# button_control_esp32.net
KiCad netlist of a schematic drawn in EAGLE
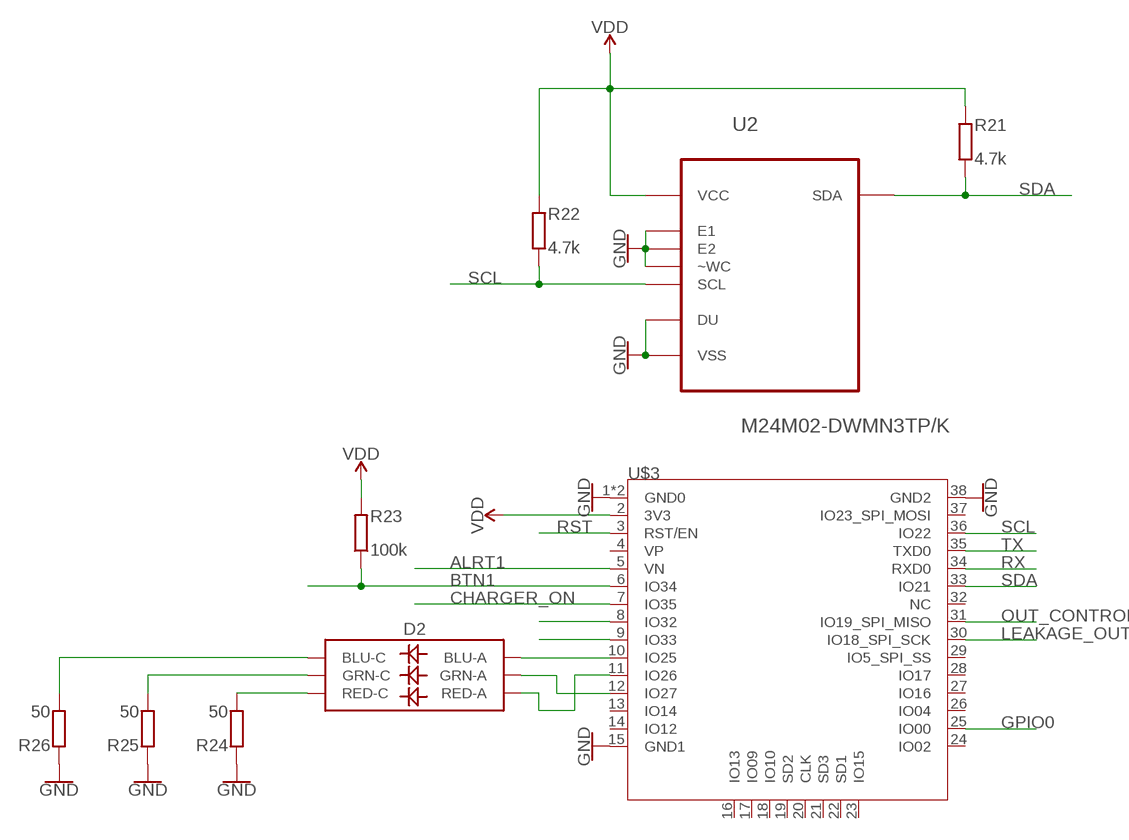
[diagram p0: schematic, sheet 1]
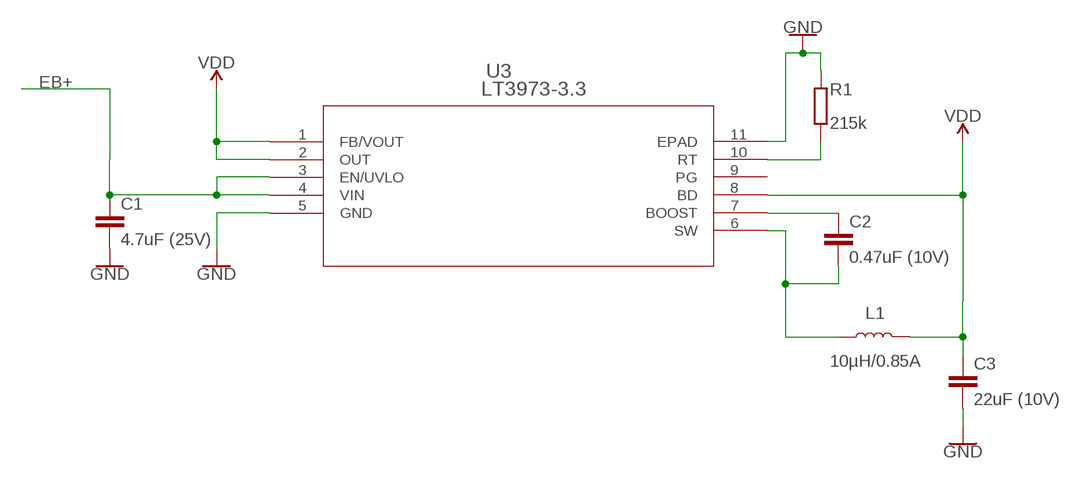
[diagram p1: schematic, sheet 2]
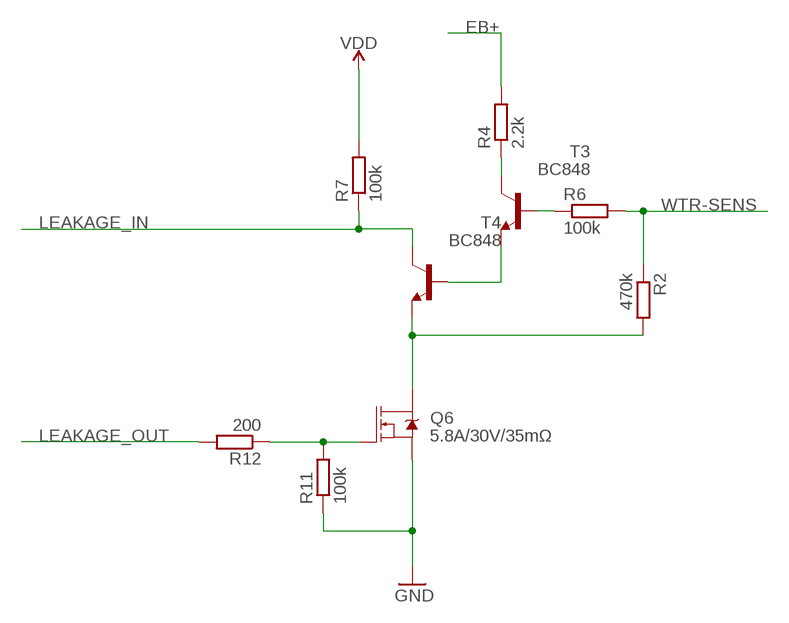
[diagram p2: schematic, sheet 3]
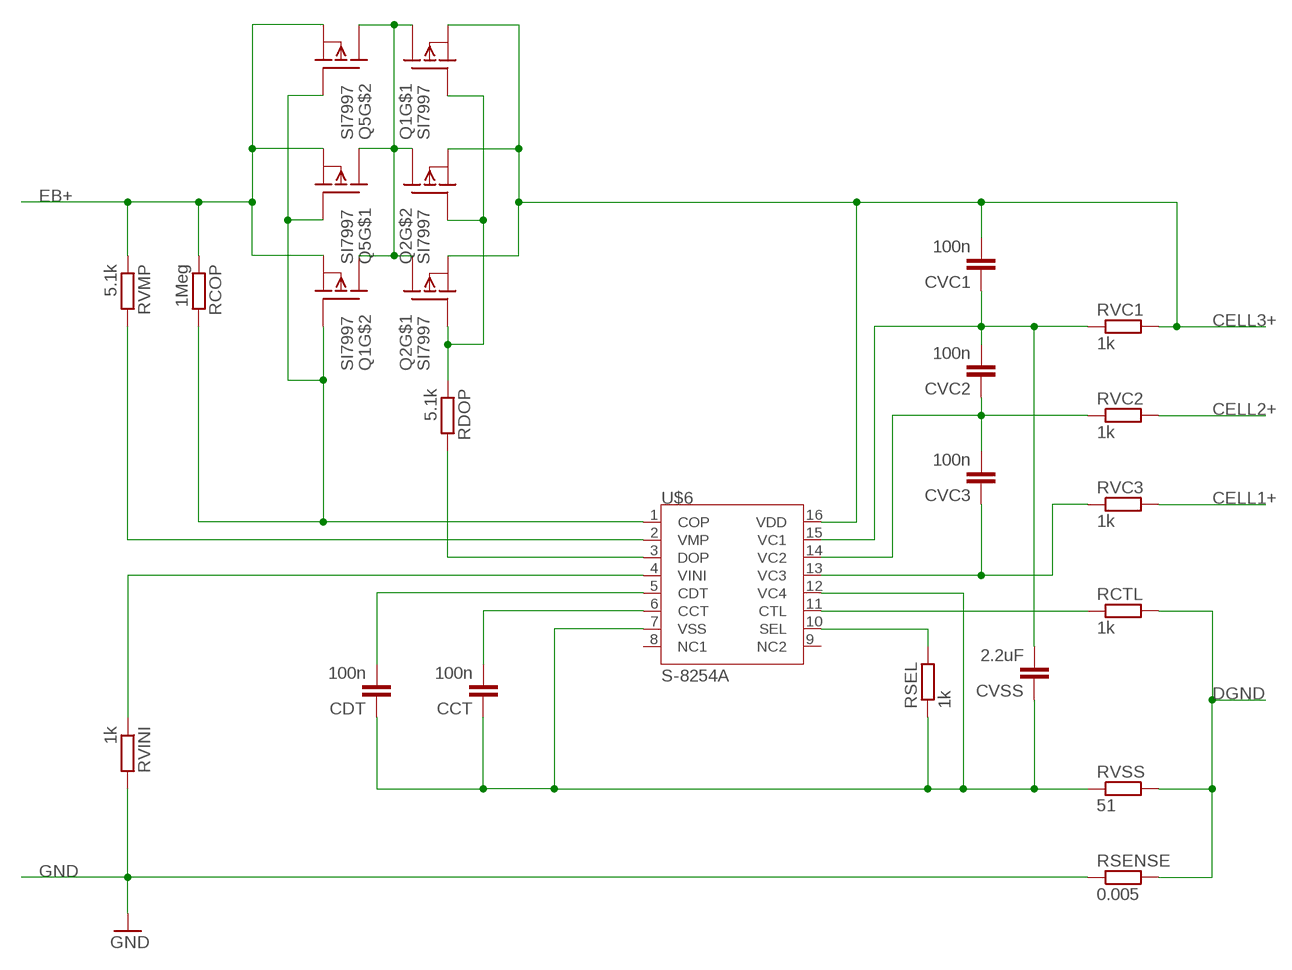
[diagram p3: schematic, sheet 4]
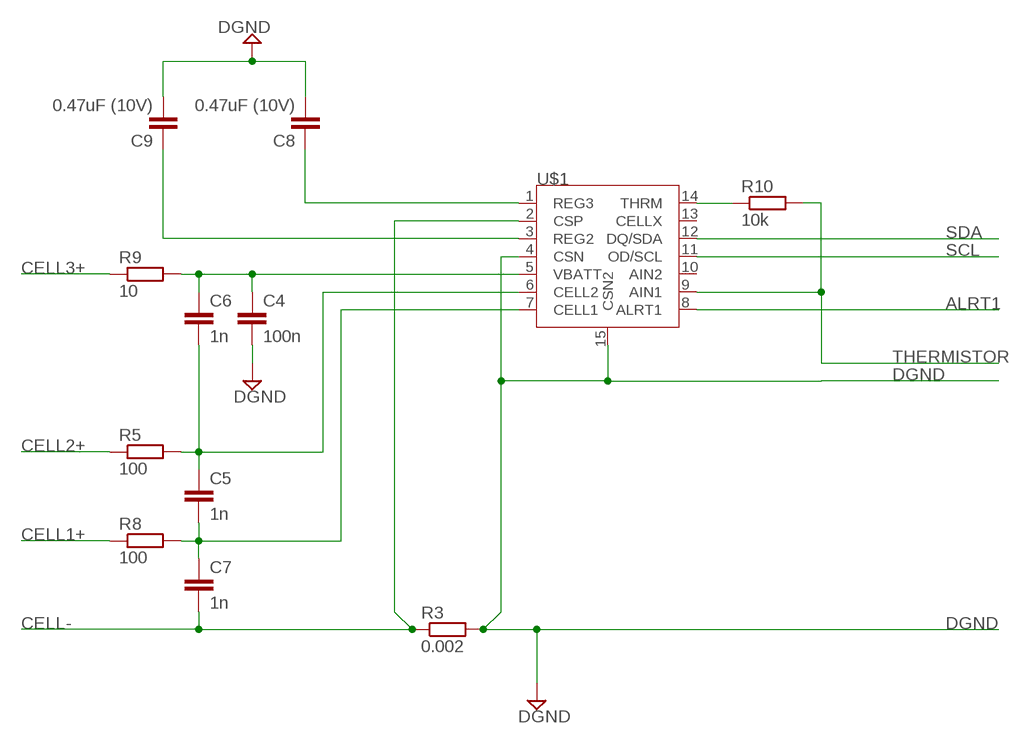
[diagram p4: schematic, sheet 5]
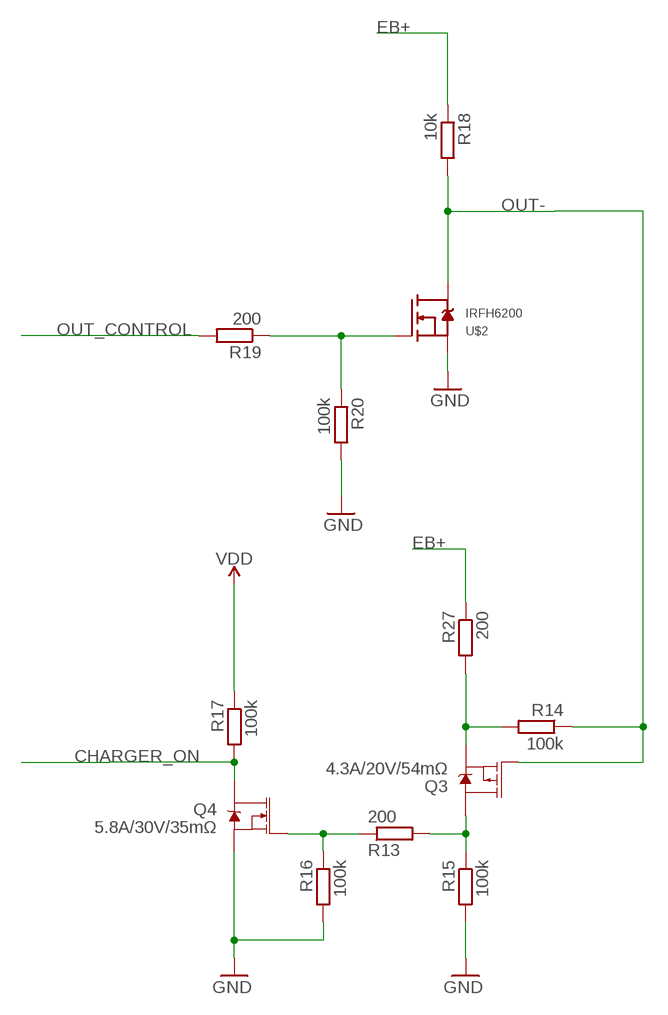
[diagram p5: schematic, sheet 6]
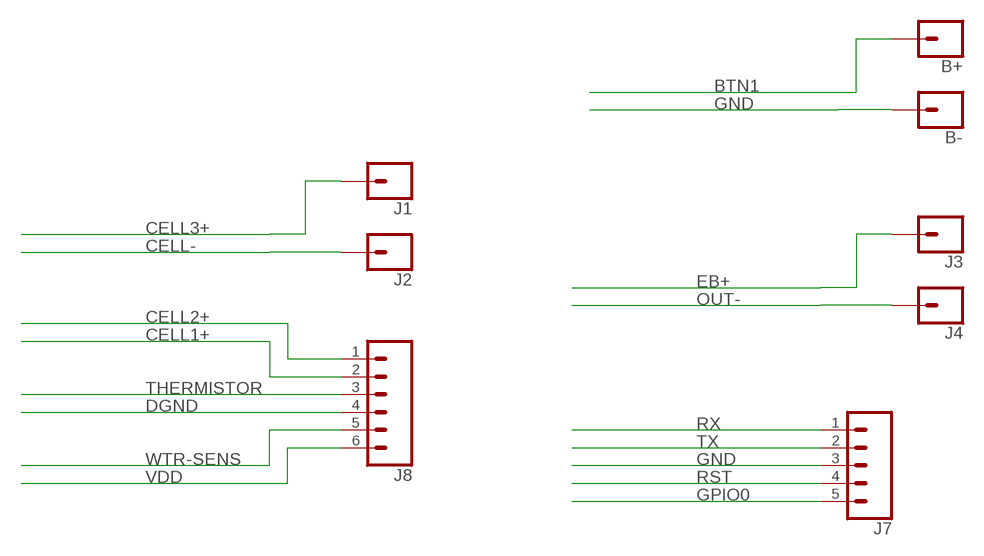
[diagram p6: schematic, sheet 7]

(export (version "E")
  (design (tool "Eeschema 10.0.6"))
  (components
    (comp (ref "Q3")
      (value "4.3A/20V/54mΩ")
      (footprint "eagle-import:SOT23-3")
      (libsource (lib "eagle-import") (part "MOSFET_PCH-IRLML2244"))
    )
    (comp (ref "Q4")
      (value "5.8A/30V/35mΩ")
      (footprint "eagle-import:SOT23-3")
      (libsource (lib "eagle-import") (part "MOSFET-NCH-AO3404A"))
    )
    (comp (ref "R13")
      (value "200")
      (footprint "eagle-import:R0603")
      (libsource (lib "eagle-import") (part "R-EU_R0603"))
    )
    (comp (ref "R14")
      (value "100k")
      (footprint "eagle-import:R0603")
      (libsource (lib "eagle-import") (part "R-EU_R0603"))
    )
    (comp (ref "R15")
      (value "100k")
      (footprint "eagle-import:R0603")
      (libsource (lib "eagle-import") (part "R-EU_R0603"))
    )
    (comp (ref "R16")
      (value "100k")
      (footprint "eagle-import:R0603")
      (libsource (lib "eagle-import") (part "R-EU_R0603"))
    )
    (comp (ref "R17")
      (value "100k")
      (footprint "eagle-import:R0603")
      (libsource (lib "eagle-import") (part "R-EU_R0603"))
    )
    (comp (ref "R18")
      (value "10k")
      (footprint "eagle-import:R0603")
      (libsource (lib "eagle-import") (part "R-EU_R0603"))
    )
    (comp (ref "R19")
      (value "200")
      (footprint "eagle-import:R0603")
      (libsource (lib "eagle-import") (part "R-EU_R0603"))
    )
    (comp (ref "R20")
      (value "100k")
      (footprint "eagle-import:R0603")
      (libsource (lib "eagle-import") (part "R-EU_R0603"))
    )
    (comp (ref "R27")
      (value "200")
      (footprint "eagle-import:R0603")
      (libsource (lib "eagle-import") (part "R-EU_R0603"))
    )
    (comp (ref "U$2")
      (value "IRFH6200")
      (footprint "eagle-import:PQFN")
      (libsource (lib "eagle-import") (part "IRFH6200"))
    )
    (comp (ref "C4")
      (value "100n")
      (footprint "eagle-import:C0603")
      (libsource (lib "eagle-import") (part "C-EUC0603"))
    )
    (comp (ref "C5")
      (value "1n")
      (footprint "eagle-import:C0603")
      (libsource (lib "eagle-import") (part "C-EUC0603"))
    )
    (comp (ref "C6")
      (value "1n")
      (footprint "eagle-import:C0603")
      (libsource (lib "eagle-import") (part "C-EUC0603"))
    )
    (comp (ref "C7")
      (value "1n")
      (footprint "eagle-import:C0603")
      (libsource (lib "eagle-import") (part "C-EUC0603"))
    )
    (comp (ref "C8")
      (value "0.47uF (10V)")
      (footprint "eagle-import:C0603K")
      (libsource (lib "eagle-import") (part "C-EUC0603K"))
    )
    (comp (ref "C9")
      (value "0.47uF (10V)")
      (footprint "eagle-import:C0603K")
      (libsource (lib "eagle-import") (part "C-EUC0603K"))
    )
    (comp (ref "R3")
      (value "0.002")
      (footprint "eagle-import:R2010")
      (libsource (lib "eagle-import") (part "resistor_348_R-EU_R2010"))
    )
    (comp (ref "R5")
      (value "100")
      (footprint "eagle-import:R0805")
      (libsource (lib "eagle-import") (part "resistor_348_R-EU_R0805"))
    )
    (comp (ref "R8")
      (value "100")
      (footprint "eagle-import:R0805")
      (libsource (lib "eagle-import") (part "resistor_348_R-EU_R0805"))
    )
    (comp (ref "R9")
      (value "10")
      (footprint "eagle-import:R0603")
      (libsource (lib "eagle-import") (part "resistor_348_R-EU_R0603"))
    )
    (comp (ref "R10")
      (value "10k")
      (footprint "eagle-import:R0603")
      (libsource (lib "eagle-import") (part "resistor_348_R-EU_R0603"))
    )
    (comp (ref "U$1")
      (value "MAX17205G")
      (footprint "eagle-import:SON40P300X300X80-15N230X170")
      (libsource (lib "eagle-import") (part "MAX17205G"))
    )
    (comp (ref "D2")
      (value "LED-RGBNO_IC")
      (footprint "eagle-import:LED-TRICOLOR-5050")
      (libsource (lib "eagle-import") (part "LED-RGBNO_IC"))
    )
    (comp (ref "R21")
      (value "4.7k")
      (footprint "eagle-import:R0603")
      (libsource (lib "eagle-import") (part "resistor_348_R-EU_R0603"))
    )
    (comp (ref "R22")
      (value "4.7k")
      (footprint "eagle-import:R0603")
      (libsource (lib "eagle-import") (part "resistor_348_R-EU_R0603"))
    )
    (comp (ref "R23")
      (value "100k")
      (footprint "eagle-import:R0603")
      (libsource (lib "eagle-import") (part "resistor_348_R-EU_R0603"))
    )
    (comp (ref "R24")
      (value "50")
      (footprint "eagle-import:R0603")
      (libsource (lib "eagle-import") (part "resistor_348_R-EU_R0603"))
    )
    (comp (ref "R25")
      (value "50")
      (footprint "eagle-import:R0603")
      (libsource (lib "eagle-import") (part "resistor_348_R-EU_R0603"))
    )
    (comp (ref "R26")
      (value "50")
      (footprint "eagle-import:R0603")
      (libsource (lib "eagle-import") (part "resistor_348_R-EU_R0603"))
    )
    (comp (ref "U$3")
      (value "ESP32")
      (footprint "eagle-import:TTGO_ESP32")
      (libsource (lib "eagle-import") (part "ESP32"))
    )
    (comp (ref "U2")
      (value "M24M02-DWMN3TP/K")
      (footprint "eagle-import:SOIC127P600X175-8N")
      (fields (field (name "DIGI-KEY_PART_NUMBER") "497-16238-1-ND") (field (name "MF") "STMicroelectronics"))
      (libsource (lib "eagle-import") (part "M24M02-DWMN3TP/K"))
    )
    (comp (ref "CCT")
      (value "100n")
      (footprint "eagle-import:C0603")
      (libsource (lib "eagle-import") (part "C-EUC0603"))
    )
    (comp (ref "CDT")
      (value "100n")
      (footprint "eagle-import:C0603")
      (libsource (lib "eagle-import") (part "C-EUC0603"))
    )
    (comp (ref "CVC1")
      (value "100n")
      (footprint "eagle-import:C0603")
      (libsource (lib "eagle-import") (part "C-EUC0603"))
    )
    (comp (ref "CVC2")
      (value "100n")
      (footprint "eagle-import:C0805K")
      (libsource (lib "eagle-import") (part "C-EUC0805K"))
    )
    (comp (ref "CVC3")
      (value "100n")
      (footprint "eagle-import:C0603")
      (libsource (lib "eagle-import") (part "C-EUC0603"))
    )
    (comp (ref "CVSS")
      (value "2.2uF")
      (footprint "eagle-import:C0805")
      (libsource (lib "eagle-import") (part "C-EUC0805"))
    )
    (comp (ref "Q1")
      (value "SI7997")
      (footprint "eagle-import:POWERPAK")
      (libsource (lib "eagle-import") (part "SI7997"))
    )
    (comp (ref "Q2")
      (value "SI7997")
      (footprint "eagle-import:POWERPAK")
      (libsource (lib "eagle-import") (part "SI7997"))
    )
    (comp (ref "Q5")
      (value "SI7997")
      (footprint "eagle-import:POWERPAK")
      (libsource (lib "eagle-import") (part "SI7997"))
    )
    (comp (ref "RCOP")
      (value "1Meg")
      (footprint "eagle-import:R0603")
      (libsource (lib "eagle-import") (part "resistor_348_R-EU_R0603"))
    )
    (comp (ref "RCTL")
      (value "1k")
      (footprint "eagle-import:R0603")
      (libsource (lib "eagle-import") (part "resistor_348_R-EU_R0603"))
    )
    (comp (ref "RDOP")
      (value "5.1k")
      (footprint "eagle-import:R0603")
      (libsource (lib "eagle-import") (part "resistor_348_R-EU_R0603"))
    )
    (comp (ref "RSEL")
      (value "1k")
      (footprint "eagle-import:R0603")
      (libsource (lib "eagle-import") (part "resistor_348_R-EU_R0603"))
    )
    (comp (ref "RSENSE")
      (value "0.005")
      (footprint "eagle-import:R2010")
      (libsource (lib "eagle-import") (part "resistor_348_R-EU_R2010"))
    )
    (comp (ref "RVC1")
      (value "1k")
      (footprint "eagle-import:R0603")
      (libsource (lib "eagle-import") (part "resistor_348_R-EU_R0603"))
    )
    (comp (ref "RVC2")
      (value "1k")
      (footprint "eagle-import:R0603")
      (libsource (lib "eagle-import") (part "resistor_348_R-EU_R0603"))
    )
    (comp (ref "RVC3")
      (value "1k")
      (footprint "eagle-import:R0603")
      (libsource (lib "eagle-import") (part "resistor_348_R-EU_R0603"))
    )
    (comp (ref "RVINI")
      (value "1k")
      (footprint "eagle-import:R0603")
      (libsource (lib "eagle-import") (part "resistor_348_R-EU_R0603"))
    )
    (comp (ref "RVMP")
      (value "5.1k")
      (footprint "eagle-import:R0603")
      (libsource (lib "eagle-import") (part "resistor_348_R-EU_R0603"))
    )
    (comp (ref "RVSS")
      (value "51")
      (footprint "eagle-import:R0603")
      (libsource (lib "eagle-import") (part "resistor_348_R-EU_R0603"))
    )
    (comp (ref "U$6")
      (value "S-8254A")
      (footprint "eagle-import:TSSOP-16")
      (libsource (lib "eagle-import") (part "S-8254A"))
    )
    (comp (ref "Q6")
      (value "5.8A/30V/35mΩ")
      (footprint "eagle-import:SOT23-3")
      (libsource (lib "eagle-import") (part "MOSFET-NCH-AO3404A"))
    )
    (comp (ref "R2")
      (value "470k")
      (footprint "eagle-import:R0603")
      (libsource (lib "eagle-import") (part "R-EU_R0603"))
    )
    (comp (ref "R4")
      (value "2.2k")
      (footprint "eagle-import:R0603")
      (libsource (lib "eagle-import") (part "R-EU_R0603"))
    )
    (comp (ref "R6")
      (value "100k")
      (footprint "eagle-import:R0603")
      (libsource (lib "eagle-import") (part "R-EU_R0603"))
    )
    (comp (ref "R7")
      (value "100k")
      (footprint "eagle-import:R0603")
      (libsource (lib "eagle-import") (part "R-EU_R0603"))
    )
    (comp (ref "R11")
      (value "100k")
      (footprint "eagle-import:R0603")
      (libsource (lib "eagle-import") (part "R-EU_R0603"))
    )
    (comp (ref "R12")
      (value "200")
      (footprint "eagle-import:R0603")
      (libsource (lib "eagle-import") (part "R-EU_R0603"))
    )
    (comp (ref "T3")
      (value "BC848")
      (footprint "eagle-import:SOT23")
      (libsource (lib "eagle-import") (part "BC848"))
    )
    (comp (ref "T4")
      (value "BC848")
      (footprint "eagle-import:SOT23")
      (fields (field (name "SPICEPREFIX") "Q"))
      (libsource (lib "eagle-import") (part "BC848"))
    )
    (comp (ref "C1")
      (value "4.7uF (25V)")
      (footprint "eagle-import:C1206")
      (libsource (lib "eagle-import") (part "C-EUC1206"))
    )
    (comp (ref "C2")
      (value "0.47uF (10V)")
      (footprint "eagle-import:C0603K")
      (libsource (lib "eagle-import") (part "C-EUC0603K"))
    )
    (comp (ref "C3")
      (value "22uF (10V)")
      (footprint "eagle-import:C1206")
      (libsource (lib "eagle-import") (part "C-EUC1206"))
    )
    (comp (ref "L1")
      (value "10µH/0.85A")
      (footprint "eagle-import:INDUCTOR_4.7UH")
      (libsource (lib "eagle-import") (part "INDUCTOR-CDRH-4.7UH"))
    )
    (comp (ref "R1")
      (value "215k")
      (footprint "eagle-import:R0603")
      (libsource (lib "eagle-import") (part "resistor_348_R-EU_R0603"))
    )
    (comp (ref "U3")
      (value "LT3973-3.3")
      (footprint "eagle-import:DFN-10_DD")
      (fields
        (field (name "DIGI-KEY_PART_NUMBER") "LT3973IDD#PBF-ND")
        (field (name "MF") "Linear Technology")
        (field (name "MP") "LT3973IDD#PBF")
      )
      (libsource (lib "eagle-import") (part "LT3973IDDPBF"))
    )
    (comp (ref "B+")
      (value "CONN_01")
      (footprint "eagle-import:1X01")
      (libsource (lib "eagle-import") (part "CONN_01"))
    )
    (comp (ref "B-")
      (value "CONN_01")
      (footprint "eagle-import:1X01")
      (libsource (lib "eagle-import") (part "CONN_01"))
    )
    (comp (ref "J1")
      (value "CONN_01PTH_2MM")
      (footprint "eagle-import:1X01_2MM")
      (libsource (lib "eagle-import") (part "CONN_01PTH_2MM"))
    )
    (comp (ref "J2")
      (value "CONN_01PTH_2MM")
      (footprint "eagle-import:1X01_2MM")
      (libsource (lib "eagle-import") (part "CONN_01PTH_2MM"))
    )
    (comp (ref "J3")
      (value "CONN_01PTH_2MM")
      (footprint "eagle-import:1X01_2MM")
      (libsource (lib "eagle-import") (part "CONN_01PTH_2MM"))
    )
    (comp (ref "J4")
      (value "CONN_01PTH_2MM")
      (footprint "eagle-import:1X01_2MM")
      (libsource (lib "eagle-import") (part "CONN_01PTH_2MM"))
    )
    (comp (ref "J7")
      (value "CONN_051.27MM")
      (footprint "eagle-import:1X05_1.27MM")
      (libsource (lib "eagle-import") (part "CONN_051.27MM"))
    )
    (comp (ref "J8")
      (value "CONN_061.27MM")
      (footprint "eagle-import:1X06_1.27MM")
      (libsource (lib "eagle-import") (part "CONN_061.27MM"))
    )
  )
  (nets
    (net (code "1") (name "ALRT1") (class "Default")
      (node (ref "U$1") (pin "8") (pinfunction "ALRT1_8") (pintype "bidirectional"))
      (node (ref "U$3") (pin "5") (pinfunction "VN_5") (pintype "bidirectional"))
    )
    (net (code "2") (name "BTN1") (class "Default")
      (node (ref "B+") (pin "1") (pinfunction "1_1") (pintype "passive"))
      (node (ref "R23") (pin "1") (pinfunction "1_1") (pintype "passive"))
      (node (ref "U$3") (pin "6") (pinfunction "IO34_6") (pintype "bidirectional"))
    )
    (net (code "3") (name "CELL-") (class "Default")
      (node (ref "C7") (pin "2") (pinfunction "2_2") (pintype "passive"))
      (node (ref "J2") (pin "1") (pinfunction "1_1") (pintype "passive"))
      (node (ref "R3") (pin "1") (pinfunction "1_1") (pintype "passive"))
      (node (ref "U$1") (pin "2") (pinfunction "CSP_2") (pintype "bidirectional"))
    )
    (net (code "4") (name "CELL1+") (class "Default")
      (node (ref "J8") (pin "2") (pinfunction "2_2") (pintype "passive"))
      (node (ref "R8") (pin "1") (pinfunction "1_1") (pintype "passive"))
      (node (ref "RVC3") (pin "2") (pinfunction "2_2") (pintype "passive"))
    )
    (net (code "5") (name "CELL2+") (class "Default")
      (node (ref "J8") (pin "1") (pinfunction "1_1") (pintype "passive"))
      (node (ref "R5") (pin "1") (pinfunction "1_1") (pintype "passive"))
      (node (ref "RVC2") (pin "2") (pinfunction "2_2") (pintype "passive"))
    )
    (net (code "6") (name "CELL3+") (class "Default")
      (node (ref "CVC1") (pin "2") (pinfunction "2_2") (pintype "passive"))
      (node (ref "J1") (pin "1") (pinfunction "1_1") (pintype "passive"))
      (node (ref "Q1") (pin "1") (pinfunction "S_1") (pintype "passive"))
      (node (ref "Q2") (pin "1") (pinfunction "S_1") (pintype "passive"))
      (node (ref "Q2") (pin "3") (pinfunction "S_3") (pintype "passive"))
      (node (ref "R9") (pin "1") (pinfunction "1_1") (pintype "passive"))
      (node (ref "RVC1") (pin "2") (pinfunction "2_2") (pintype "passive"))
      (node (ref "U$6") (pin "16") (pinfunction "VDD_16") (pintype "bidirectional"))
    )
    (net (code "7") (name "CHARGER_ON") (class "Default")
      (node (ref "Q4") (pin "3") (pinfunction "D_3") (pintype "bidirectional"))
      (node (ref "R17") (pin "2") (pinfunction "2_2") (pintype "passive"))
      (node (ref "U$3") (pin "7") (pinfunction "IO35_7") (pintype "bidirectional"))
    )
    (net (code "8") (name "DGND") (class "Default")
      (node (ref "C4") (pin "2") (pinfunction "2_2") (pintype "passive"))
      (node (ref "C8") (pin "2") (pinfunction "2_2") (pintype "passive"))
      (node (ref "C9") (pin "2") (pinfunction "2_2") (pintype "passive"))
      (node (ref "J8") (pin "4") (pinfunction "4_4") (pintype "passive"))
      (node (ref "R3") (pin "2") (pinfunction "2_2") (pintype "passive"))
      (node (ref "RCTL") (pin "2") (pinfunction "2_2") (pintype "passive"))
      (node (ref "RSENSE") (pin "2") (pinfunction "2_2") (pintype "passive"))
      (node (ref "RVSS") (pin "2") (pinfunction "2_2") (pintype "passive"))
      (node (ref "U$1") (pin "15") (pinfunction "CSN2_15") (pintype "bidirectional"))
      (node (ref "U$1") (pin "4") (pinfunction "CSN_4") (pintype "bidirectional"))
    )
    (net (code "9") (name "EB+") (class "Default")
      (node (ref "C1") (pin "1") (pinfunction "1_1") (pintype "passive"))
      (node (ref "J3") (pin "1") (pinfunction "1_1") (pintype "passive"))
      (node (ref "Q1") (pin "3") (pinfunction "S_3") (pintype "passive"))
      (node (ref "Q5") (pin "1") (pinfunction "S_1") (pintype "passive"))
      (node (ref "Q5") (pin "3") (pinfunction "S_3") (pintype "passive"))
      (node (ref "R18") (pin "1") (pinfunction "1_1") (pintype "passive"))
      (node (ref "R27") (pin "1") (pinfunction "1_1") (pintype "passive"))
      (node (ref "R4") (pin "2") (pinfunction "2_2") (pintype "passive"))
      (node (ref "RCOP") (pin "1") (pinfunction "1_1") (pintype "passive"))
      (node (ref "RVMP") (pin "1") (pinfunction "1_1") (pintype "passive"))
      (node (ref "U3") (pin "3") (pinfunction "EN/UVLO_3") (pintype "bidirectional"))
      (node (ref "U3") (pin "4") (pinfunction "VIN_4") (pintype "input"))
    )
    (net (code "10") (name "GND") (class "Default")
      (node (ref "B-") (pin "1") (pinfunction "1_1") (pintype "passive"))
      (node (ref "C1") (pin "2") (pinfunction "2_2") (pintype "passive"))
      (node (ref "C3") (pin "2") (pinfunction "2_2") (pintype "passive"))
      (node (ref "J7") (pin "3") (pinfunction "3_3") (pintype "passive"))
      (node (ref "Q4") (pin "2") (pinfunction "S_2") (pintype "bidirectional"))
      (node (ref "Q6") (pin "2") (pinfunction "S_2") (pintype "bidirectional"))
      (node (ref "R1") (pin "2") (pinfunction "2_2") (pintype "passive"))
      (node (ref "R11") (pin "1") (pinfunction "1_1") (pintype "passive"))
      (node (ref "R15") (pin "2") (pinfunction "2_2") (pintype "passive"))
      (node (ref "R16") (pin "2") (pinfunction "2_2") (pintype "passive"))
      (node (ref "R20") (pin "2") (pinfunction "2_2") (pintype "passive"))
      (node (ref "R24") (pin "2") (pinfunction "2_2") (pintype "passive"))
      (node (ref "R25") (pin "2") (pinfunction "2_2") (pintype "passive"))
      (node (ref "R26") (pin "2") (pinfunction "2_2") (pintype "passive"))
      (node (ref "RSENSE") (pin "1") (pinfunction "1_1") (pintype "passive"))
      (node (ref "RVINI") (pin "2") (pinfunction "2_2") (pintype "passive"))
      (node (ref "U$2") (pin "1") (pinfunction "S_1") (pintype "power_in"))
      (node (ref "U$2") (pin "2") (pinfunction "S_2") (pintype "power_in"))
      (node (ref "U$2") (pin "3") (pinfunction "S_3") (pintype "power_in"))
      (node (ref "U$3") (pin "1") (pinfunction "GND0_1") (pintype "bidirectional"))
      (node (ref "U$3") (pin "15") (pinfunction "GND1_15") (pintype "bidirectional"))
      (node (ref "U$3") (pin "38") (pinfunction "GND2_38") (pintype "bidirectional"))
      (node (ref "U$3") (pin "P$1") (pinfunction "GND0_P$1") (pintype "bidirectional"))
      (node (ref "U2") (pin "1") (pinfunction "DU_1") (pintype "input"))
      (node (ref "U2") (pin "2") (pinfunction "E1_2") (pintype "input"))
      (node (ref "U2") (pin "3") (pinfunction "E2_3") (pintype "input"))
      (node (ref "U2") (pin "4") (pinfunction "VSS_4") (pintype "power_in"))
      (node (ref "U2") (pin "7") (pinfunction "~{WC}_7") (pintype "input"))
      (node (ref "U3") (pin "11") (pinfunction "EPAD_11") (pintype "passive"))
      (node (ref "U3") (pin "5") (pinfunction "GND_5") (pintype "power_in"))
    )
    (net (code "11") (name "GPIO0") (class "Default")
      (node (ref "J7") (pin "5") (pinfunction "5_5") (pintype "passive"))
      (node (ref "U$3") (pin "25") (pinfunction "IO00_25") (pintype "bidirectional"))
    )
    (net (code "12") (name "LEAKAGE_IN") (class "Default")
      (node (ref "R7") (pin "1") (pinfunction "1_1") (pintype "passive"))
      (node (ref "T4") (pin "3") (pinfunction "C_3") (pintype "passive"))
    )
    (net (code "13") (name "LEAKAGE_OUT") (class "Default")
      (node (ref "R12") (pin "2") (pinfunction "2_2") (pintype "passive"))
      (node (ref "U$3") (pin "30") (pinfunction "IO18_SPI_SCK_30") (pintype "bidirectional"))
    )
    (net (code "14") (name "Net-(D2-BLU-A)") (class "Default")
      (node (ref "D2") (pin "3") (pinfunction "BLU-A_3") (pintype "bidirectional"))
      (node (ref "U$3") (pin "10") (pinfunction "IO25_10") (pintype "bidirectional"))
    )
    (net (code "15") (name "Net-(D2-BLU-C)") (class "Default")
      (node (ref "D2") (pin "4") (pinfunction "BLU-C_4") (pintype "bidirectional"))
      (node (ref "R26") (pin "1") (pinfunction "1_1") (pintype "passive"))
    )
    (net (code "16") (name "Net-(D2-GRN-A)") (class "Default")
      (node (ref "D2") (pin "1") (pinfunction "GRN-A_1") (pintype "bidirectional"))
      (node (ref "U$3") (pin "12") (pinfunction "IO27_12") (pintype "bidirectional"))
    )
    (net (code "17") (name "Net-(D2-GRN-C)") (class "Default")
      (node (ref "D2") (pin "6") (pinfunction "GRN-C_6") (pintype "bidirectional"))
      (node (ref "R25") (pin "1") (pinfunction "1_1") (pintype "passive"))
    )
    (net (code "18") (name "Net-(D2-RED-A)") (class "Default")
      (node (ref "D2") (pin "2") (pinfunction "RED-A_2") (pintype "bidirectional"))
      (node (ref "U$3") (pin "11") (pinfunction "IO26_11") (pintype "bidirectional"))
    )
    (net (code "19") (name "Net-(D2-RED-C)") (class "Default")
      (node (ref "D2") (pin "5") (pinfunction "RED-C_5") (pintype "bidirectional"))
      (node (ref "R24") (pin "1") (pinfunction "1_1") (pintype "passive"))
    )
    (net (code "20") (name "Net-(L1-1)") (class "Default")
      (node (ref "C2") (pin "2") (pinfunction "2_2") (pintype "passive"))
      (node (ref "L1") (pin "P$1") (pinfunction "1_P$1") (pintype "passive"))
      (node (ref "U3") (pin "6") (pinfunction "SW_6") (pintype "output"))
    )
    (net (code "21") (name "Net-(Q1A-D-Pad7)") (class "Default")
      (node (ref "Q1") (pin "5") (pinfunction "D_5") (pintype "passive"))
      (node (ref "Q1") (pin "5_6") (pinfunction "D_5_6") (pintype "passive"))
      (node (ref "Q1") (pin "6") (pinfunction "D_6") (pintype "passive"))
      (node (ref "Q1") (pin "7") (pinfunction "D_7") (pintype "passive"))
      (node (ref "Q1") (pin "7_8") (pinfunction "D_7_8") (pintype "passive"))
      (node (ref "Q1") (pin "8") (pinfunction "D_8") (pintype "passive"))
      (node (ref "Q2") (pin "5") (pinfunction "D_5") (pintype "passive"))
      (node (ref "Q2") (pin "5_6") (pinfunction "D_5_6") (pintype "passive"))
      (node (ref "Q2") (pin "6") (pinfunction "D_6") (pintype "passive"))
      (node (ref "Q2") (pin "7") (pinfunction "D_7") (pintype "passive"))
      (node (ref "Q2") (pin "7_8") (pinfunction "D_7_8") (pintype "passive"))
      (node (ref "Q2") (pin "8") (pinfunction "D_8") (pintype "passive"))
      (node (ref "Q5") (pin "5") (pinfunction "D_5") (pintype "passive"))
      (node (ref "Q5") (pin "5_6") (pinfunction "D_5_6") (pintype "passive"))
      (node (ref "Q5") (pin "6") (pinfunction "D_6") (pintype "passive"))
      (node (ref "Q5") (pin "7") (pinfunction "D_7") (pintype "passive"))
      (node (ref "Q5") (pin "7_8") (pinfunction "D_7_8") (pintype "passive"))
      (node (ref "Q5") (pin "8") (pinfunction "D_8") (pintype "passive"))
    )
    (net (code "22") (name "Net-(Q1A-G)") (class "Default")
      (node (ref "Q1") (pin "2") (pinfunction "G_2") (pintype "passive"))
      (node (ref "Q2") (pin "2") (pinfunction "G_2") (pintype "passive"))
      (node (ref "Q2") (pin "4") (pinfunction "G_4") (pintype "passive"))
      (node (ref "RDOP") (pin "1") (pinfunction "1_1") (pintype "passive"))
    )
    (net (code "23") (name "Net-(Q1B-G)") (class "Default")
      (node (ref "Q1") (pin "4") (pinfunction "G_4") (pintype "passive"))
      (node (ref "Q5") (pin "2") (pinfunction "G_2") (pintype "passive"))
      (node (ref "Q5") (pin "4") (pinfunction "G_4") (pintype "passive"))
      (node (ref "RCOP") (pin "2") (pinfunction "2_2") (pintype "passive"))
      (node (ref "U$6") (pin "1") (pinfunction "COP_1") (pintype "bidirectional"))
    )
    (net (code "24") (name "Net-(Q3-D)") (class "Default")
      (node (ref "Q3") (pin "3") (pinfunction "D_3") (pintype "bidirectional"))
      (node (ref "R13") (pin "2") (pinfunction "2_2") (pintype "passive"))
      (node (ref "R15") (pin "1") (pinfunction "1_1") (pintype "passive"))
    )
    (net (code "25") (name "Net-(Q3-S)") (class "Default")
      (node (ref "Q3") (pin "2") (pinfunction "S_2") (pintype "bidirectional"))
      (node (ref "R14") (pin "2") (pinfunction "2_2") (pintype "passive"))
      (node (ref "R27") (pin "2") (pinfunction "2_2") (pintype "passive"))
    )
    (net (code "26") (name "Net-(Q4-G)") (class "Default")
      (node (ref "Q4") (pin "1") (pinfunction "G_1") (pintype "bidirectional"))
      (node (ref "R13") (pin "1") (pinfunction "1_1") (pintype "passive"))
      (node (ref "R16") (pin "1") (pinfunction "1_1") (pintype "passive"))
    )
    (net (code "27") (name "Net-(Q6-D)") (class "Default")
      (node (ref "Q6") (pin "3") (pinfunction "D_3") (pintype "bidirectional"))
      (node (ref "R2") (pin "2") (pinfunction "2_2") (pintype "passive"))
      (node (ref "T4") (pin "2") (pinfunction "E_2") (pintype "passive"))
    )
    (net (code "28") (name "Net-(Q6-G)") (class "Default")
      (node (ref "Q6") (pin "1") (pinfunction "G_1") (pintype "bidirectional"))
      (node (ref "R11") (pin "2") (pinfunction "2_2") (pintype "passive"))
      (node (ref "R12") (pin "1") (pinfunction "1_1") (pintype "passive"))
    )
    (net (code "29") (name "Net-(T3-B)") (class "Default")
      (node (ref "R6") (pin "1") (pinfunction "1_1") (pintype "passive"))
      (node (ref "T3") (pin "1") (pinfunction "B_1") (pintype "passive"))
    )
    (net (code "30") (name "Net-(T3-C)") (class "Default")
      (node (ref "R4") (pin "1") (pinfunction "1_1") (pintype "passive"))
      (node (ref "T3") (pin "3") (pinfunction "C_3") (pintype "passive"))
    )
    (net (code "31") (name "Net-(T3-E)") (class "Default")
      (node (ref "T3") (pin "2") (pinfunction "E_2") (pintype "passive"))
      (node (ref "T4") (pin "1") (pinfunction "B_1") (pintype "passive"))
    )
    (net (code "32") (name "Net-(U$1-CELL1)") (class "Default")
      (node (ref "C5") (pin "2") (pinfunction "2_2") (pintype "passive"))
      (node (ref "C7") (pin "1") (pinfunction "1_1") (pintype "passive"))
      (node (ref "R8") (pin "2") (pinfunction "2_2") (pintype "passive"))
      (node (ref "U$1") (pin "7") (pinfunction "CELL1_7") (pintype "bidirectional"))
    )
    (net (code "33") (name "Net-(U$1-CELL2)") (class "Default")
      (node (ref "C5") (pin "1") (pinfunction "1_1") (pintype "passive"))
      (node (ref "C6") (pin "2") (pinfunction "2_2") (pintype "passive"))
      (node (ref "R5") (pin "2") (pinfunction "2_2") (pintype "passive"))
      (node (ref "U$1") (pin "6") (pinfunction "CELL2_6") (pintype "bidirectional"))
    )
    (net (code "34") (name "Net-(U$1-REG2)") (class "Default")
      (node (ref "C9") (pin "1") (pinfunction "1_1") (pintype "passive"))
      (node (ref "U$1") (pin "3") (pinfunction "REG2_3") (pintype "bidirectional"))
    )
    (net (code "35") (name "Net-(U$1-REG3)") (class "Default")
      (node (ref "C8") (pin "1") (pinfunction "1_1") (pintype "passive"))
      (node (ref "U$1") (pin "1") (pinfunction "REG3_1") (pintype "bidirectional"))
    )
    (net (code "36") (name "Net-(U$1-THRM)") (class "Default")
      (node (ref "R10") (pin "1") (pinfunction "1_1") (pintype "passive"))
      (node (ref "U$1") (pin "14") (pinfunction "THRM_14") (pintype "bidirectional"))
    )
    (net (code "37") (name "Net-(U$1-VBATT)") (class "Default")
      (node (ref "C4") (pin "1") (pinfunction "1_1") (pintype "passive"))
      (node (ref "C6") (pin "1") (pinfunction "1_1") (pintype "passive"))
      (node (ref "R9") (pin "2") (pinfunction "2_2") (pintype "passive"))
      (node (ref "U$1") (pin "5") (pinfunction "VBATT_5") (pintype "bidirectional"))
    )
    (net (code "38") (name "Net-(U$2-G)") (class "Default")
      (node (ref "R19") (pin "1") (pinfunction "1_1") (pintype "passive"))
      (node (ref "R20") (pin "1") (pinfunction "1_1") (pintype "passive"))
      (node (ref "U$2") (pin "4") (pinfunction "G_4") (pintype "bidirectional"))
    )
    (net (code "39") (name "Net-(U$6-CCT)") (class "Default")
      (node (ref "CCT") (pin "2") (pinfunction "2_2") (pintype "passive"))
      (node (ref "U$6") (pin "6") (pinfunction "CCT_6") (pintype "bidirectional"))
    )
    (net (code "40") (name "Net-(U$6-CDT)") (class "Default")
      (node (ref "CDT") (pin "2") (pinfunction "2_2") (pintype "passive"))
      (node (ref "U$6") (pin "5") (pinfunction "CDT_5") (pintype "bidirectional"))
    )
    (net (code "41") (name "Net-(U$6-CTL)") (class "Default")
      (node (ref "RCTL") (pin "1") (pinfunction "1_1") (pintype "passive"))
      (node (ref "U$6") (pin "11") (pinfunction "CTL_11") (pintype "bidirectional"))
    )
    (net (code "42") (name "Net-(U$6-DOP)") (class "Default")
      (node (ref "RDOP") (pin "2") (pinfunction "2_2") (pintype "passive"))
      (node (ref "U$6") (pin "3") (pinfunction "DOP_3") (pintype "bidirectional"))
    )
    (net (code "43") (name "Net-(U$6-SEL)") (class "Default")
      (node (ref "RSEL") (pin "2") (pinfunction "2_2") (pintype "passive"))
      (node (ref "U$6") (pin "10") (pinfunction "SEL_10") (pintype "bidirectional"))
    )
    (net (code "44") (name "Net-(U$6-VC1)") (class "Default")
      (node (ref "CVC1") (pin "1") (pinfunction "1_1") (pintype "passive"))
      (node (ref "CVC2") (pin "2") (pinfunction "2_2") (pintype "passive"))
      (node (ref "CVSS") (pin "2") (pinfunction "2_2") (pintype "passive"))
      (node (ref "RVC1") (pin "1") (pinfunction "1_1") (pintype "passive"))
      (node (ref "U$6") (pin "15") (pinfunction "VC1_15") (pintype "bidirectional"))
    )
    (net (code "45") (name "Net-(U$6-VC2)") (class "Default")
      (node (ref "CVC2") (pin "1") (pinfunction "1_1") (pintype "passive"))
      (node (ref "CVC3") (pin "2") (pinfunction "2_2") (pintype "passive"))
      (node (ref "RVC2") (pin "1") (pinfunction "1_1") (pintype "passive"))
      (node (ref "U$6") (pin "14") (pinfunction "VC2_14") (pintype "bidirectional"))
    )
    (net (code "46") (name "Net-(U$6-VC3)") (class "Default")
      (node (ref "CVC3") (pin "1") (pinfunction "1_1") (pintype "passive"))
      (node (ref "RVC3") (pin "1") (pinfunction "1_1") (pintype "passive"))
      (node (ref "U$6") (pin "13") (pinfunction "VC3_13") (pintype "bidirectional"))
    )
    (net (code "47") (name "Net-(U$6-VC4)") (class "Default")
      (node (ref "CCT") (pin "1") (pinfunction "1_1") (pintype "passive"))
      (node (ref "CDT") (pin "1") (pinfunction "1_1") (pintype "passive"))
      (node (ref "CVSS") (pin "1") (pinfunction "1_1") (pintype "passive"))
      (node (ref "RSEL") (pin "1") (pinfunction "1_1") (pintype "passive"))
      (node (ref "RVSS") (pin "1") (pinfunction "1_1") (pintype "passive"))
      (node (ref "U$6") (pin "12") (pinfunction "VC4_12") (pintype "bidirectional"))
      (node (ref "U$6") (pin "7") (pinfunction "VSS_7") (pintype "bidirectional"))
    )
    (net (code "48") (name "Net-(U$6-VINI)") (class "Default")
      (node (ref "RVINI") (pin "1") (pinfunction "1_1") (pintype "passive"))
      (node (ref "U$6") (pin "4") (pinfunction "VINI_4") (pintype "bidirectional"))
    )
    (net (code "49") (name "Net-(U$6-VMP)") (class "Default")
      (node (ref "RVMP") (pin "2") (pinfunction "2_2") (pintype "passive"))
      (node (ref "U$6") (pin "2") (pinfunction "VMP_2") (pintype "bidirectional"))
    )
    (net (code "50") (name "Net-(U3-BOOST)") (class "Default")
      (node (ref "C2") (pin "1") (pinfunction "1_1") (pintype "passive"))
      (node (ref "U3") (pin "7") (pinfunction "BOOST_7") (pintype "input"))
    )
    (net (code "51") (name "Net-(U3-RT)") (class "Default")
      (node (ref "R1") (pin "1") (pinfunction "1_1") (pintype "passive"))
      (node (ref "U3") (pin "10") (pinfunction "RT_10") (pintype "passive"))
    )
    (net (code "52") (name "OUT-") (class "Default")
      (node (ref "J4") (pin "1") (pinfunction "1_1") (pintype "passive"))
      (node (ref "Q3") (pin "1") (pinfunction "G_1") (pintype "bidirectional"))
      (node (ref "R14") (pin "1") (pinfunction "1_1") (pintype "passive"))
      (node (ref "R18") (pin "2") (pinfunction "2_2") (pintype "passive"))
      (node (ref "U$2") (pin "5") (pinfunction "D_5") (pintype "power_in"))
      (node (ref "U$2") (pin "6") (pinfunction "D_6") (pintype "power_in"))
      (node (ref "U$2") (pin "7") (pinfunction "D_7") (pintype "power_in"))
      (node (ref "U$2") (pin "8") (pinfunction "D_8") (pintype "power_in"))
      (node (ref "U$2") (pin "9") (pinfunction "D_9") (pintype "power_in"))
    )
    (net (code "53") (name "OUT_CONTROL") (class "Default")
      (node (ref "R19") (pin "2") (pinfunction "2_2") (pintype "passive"))
      (node (ref "U$3") (pin "31") (pinfunction "IO19_SPI_MISO_31") (pintype "bidirectional"))
    )
    (net (code "54") (name "RST") (class "Default")
      (node (ref "J7") (pin "4") (pinfunction "4_4") (pintype "passive"))
      (node (ref "U$3") (pin "3") (pinfunction "RST/EN_3") (pintype "bidirectional"))
    )
    (net (code "55") (name "RX") (class "Default")
      (node (ref "J7") (pin "1") (pinfunction "1_1") (pintype "passive"))
      (node (ref "U$3") (pin "34") (pinfunction "RXD0_34") (pintype "bidirectional"))
    )
    (net (code "56") (name "SCL") (class "Default")
      (node (ref "R22") (pin "1") (pinfunction "1_1") (pintype "passive"))
      (node (ref "U$1") (pin "11") (pinfunction "OD/SCL_11") (pintype "bidirectional"))
      (node (ref "U$3") (pin "36") (pinfunction "IO22_36") (pintype "bidirectional"))
      (node (ref "U2") (pin "6") (pinfunction "SCL_6") (pintype "input"))
    )
    (net (code "57") (name "SDA") (class "Default")
      (node (ref "R21") (pin "1") (pinfunction "1_1") (pintype "passive"))
      (node (ref "U$1") (pin "12") (pinfunction "DQ/SDA_12") (pintype "bidirectional"))
      (node (ref "U$3") (pin "33") (pinfunction "IO21_33") (pintype "bidirectional"))
      (node (ref "U2") (pin "5") (pinfunction "SDA_5") (pintype "output"))
    )
    (net (code "58") (name "THERMISTOR") (class "Default")
      (node (ref "J8") (pin "3") (pinfunction "3_3") (pintype "passive"))
      (node (ref "R10") (pin "2") (pinfunction "2_2") (pintype "passive"))
      (node (ref "U$1") (pin "9") (pinfunction "AIN1_9") (pintype "bidirectional"))
    )
    (net (code "59") (name "TX") (class "Default")
      (node (ref "J7") (pin "2") (pinfunction "2_2") (pintype "passive"))
      (node (ref "U$3") (pin "35") (pinfunction "TXD0_35") (pintype "bidirectional"))
    )
    (net (code "60") (name "VDD") (class "Default")
      (node (ref "C3") (pin "1") (pinfunction "1_1") (pintype "passive"))
      (node (ref "J8") (pin "6") (pinfunction "6_6") (pintype "passive"))
      (node (ref "L1") (pin "P$2") (pinfunction "2_P$2") (pintype "passive"))
      (node (ref "R17") (pin "1") (pinfunction "1_1") (pintype "passive"))
      (node (ref "R21") (pin "2") (pinfunction "2_2") (pintype "passive"))
      (node (ref "R22") (pin "2") (pinfunction "2_2") (pintype "passive"))
      (node (ref "R23") (pin "2") (pinfunction "2_2") (pintype "passive"))
      (node (ref "R7") (pin "2") (pinfunction "2_2") (pintype "passive"))
      (node (ref "U$3") (pin "2") (pinfunction "3V3_2") (pintype "bidirectional"))
      (node (ref "U2") (pin "8") (pinfunction "VCC_8") (pintype "power_in"))
      (node (ref "U3") (pin "1") (pinfunction "FB/VOUT_1") (pintype "bidirectional"))
      (node (ref "U3") (pin "2") (pinfunction "OUT_2") (pintype "output"))
      (node (ref "U3") (pin "8") (pinfunction "BD_8") (pintype "passive"))
    )
    (net (code "61") (name "WTR-SENS") (class "Default")
      (node (ref "J8") (pin "5") (pinfunction "5_5") (pintype "passive"))
      (node (ref "R2") (pin "1") (pinfunction "1_1") (pintype "passive"))
      (node (ref "R6") (pin "2") (pinfunction "2_2") (pintype "passive"))
    )
    (net (code "62") (name "unconnected-(U$1-AIN2-Pad10)") (class "Default")
      (node (ref "U$1") (pin "10") (pinfunction "AIN2_10") (pintype "bidirectional"))
    )
    (net (code "63") (name "unconnected-(U$1-CELLX-Pad13)") (class "Default")
      (node (ref "U$1") (pin "13") (pinfunction "CELLX_13") (pintype "bidirectional"))
    )
    (net (code "64") (name "unconnected-(U$3-CLK-Pad20)") (class "Default")
      (node (ref "U$3") (pin "20") (pinfunction "CLK_20") (pintype "bidirectional"))
    )
    (net (code "65") (name "unconnected-(U$3-IO02-Pad24)") (class "Default")
      (node (ref "U$3") (pin "24") (pinfunction "IO02_24") (pintype "bidirectional"))
    )
    (net (code "66") (name "unconnected-(U$3-IO04-Pad26)") (class "Default")
      (node (ref "U$3") (pin "26") (pinfunction "IO04_26") (pintype "bidirectional"))
    )
    (net (code "67") (name "unconnected-(U$3-IO5_SPI_SS-Pad29)") (class "Default")
      (node (ref "U$3") (pin "29") (pinfunction "IO5_SPI_SS_29") (pintype "bidirectional"))
    )
    (net (code "68") (name "unconnected-(U$3-IO09-Pad17)") (class "Default")
      (node (ref "U$3") (pin "17") (pinfunction "IO09_17") (pintype "bidirectional"))
    )
    (net (code "69") (name "unconnected-(U$3-IO10-Pad18)") (class "Default")
      (node (ref "U$3") (pin "18") (pinfunction "IO10_18") (pintype "bidirectional"))
    )
    (net (code "70") (name "unconnected-(U$3-IO12-Pad14)") (class "Default")
      (node (ref "U$3") (pin "14") (pinfunction "IO12_14") (pintype "bidirectional"))
    )
    (net (code "71") (name "unconnected-(U$3-IO13-Pad16)") (class "Default")
      (node (ref "U$3") (pin "16") (pinfunction "IO13_16") (pintype "bidirectional"))
    )
    (net (code "72") (name "unconnected-(U$3-IO14-Pad13)") (class "Default")
      (node (ref "U$3") (pin "13") (pinfunction "IO14_13") (pintype "bidirectional"))
    )
    (net (code "73") (name "unconnected-(U$3-IO15-Pad23)") (class "Default")
      (node (ref "U$3") (pin "23") (pinfunction "IO15_23") (pintype "bidirectional"))
    )
    (net (code "74") (name "unconnected-(U$3-IO16-Pad27)") (class "Default")
      (node (ref "U$3") (pin "27") (pinfunction "IO16_27") (pintype "bidirectional"))
    )
    (net (code "75") (name "unconnected-(U$3-IO17-Pad28)") (class "Default")
      (node (ref "U$3") (pin "28") (pinfunction "IO17_28") (pintype "bidirectional"))
    )
    (net (code "76") (name "unconnected-(U$3-IO23_SPI_MOSI-Pad37)") (class "Default")
      (node (ref "U$3") (pin "37") (pinfunction "IO23_SPI_MOSI_37") (pintype "bidirectional"))
    )
    (net (code "77") (name "unconnected-(U$3-IO32-Pad8)") (class "Default")
      (node (ref "U$3") (pin "8") (pinfunction "IO32_8") (pintype "bidirectional"))
    )
    (net (code "78") (name "unconnected-(U$3-IO33-Pad9)") (class "Default")
      (node (ref "U$3") (pin "9") (pinfunction "IO33_9") (pintype "bidirectional"))
    )
    (net (code "79") (name "unconnected-(U$3-NC-Pad32)") (class "Default")
      (node (ref "U$3") (pin "32") (pinfunction "NC_32") (pintype "bidirectional"))
    )
    (net (code "80") (name "unconnected-(U$3-SD1-Pad22)") (class "Default")
      (node (ref "U$3") (pin "22") (pinfunction "SD1_22") (pintype "bidirectional"))
    )
    (net (code "81") (name "unconnected-(U$3-SD2-Pad19)") (class "Default")
      (node (ref "U$3") (pin "19") (pinfunction "SD2_19") (pintype "bidirectional"))
    )
    (net (code "82") (name "unconnected-(U$3-SD3-Pad21)") (class "Default")
      (node (ref "U$3") (pin "21") (pinfunction "SD3_21") (pintype "bidirectional"))
    )
    (net (code "83") (name "unconnected-(U$3-VP-Pad4)") (class "Default")
      (node (ref "U$3") (pin "4") (pinfunction "VP_4") (pintype "bidirectional"))
    )
    (net (code "84") (name "unconnected-(U$6-NC1-Pad8)") (class "Default")
      (node (ref "U$6") (pin "8") (pinfunction "NC1_8") (pintype "bidirectional"))
    )
    (net (code "85") (name "unconnected-(U$6-NC2-Pad9)") (class "Default")
      (node (ref "U$6") (pin "9") (pinfunction "NC2_9") (pintype "bidirectional"))
    )
    (net (code "86") (name "unconnected-(U3-PG-Pad9)") (class "Default")
      (node (ref "U3") (pin "9") (pinfunction "PG_9") (pintype "output"))
    )
  )
)
